# High_Current_Board.net
KiCad netlist of a schematic drawn in EAGLE
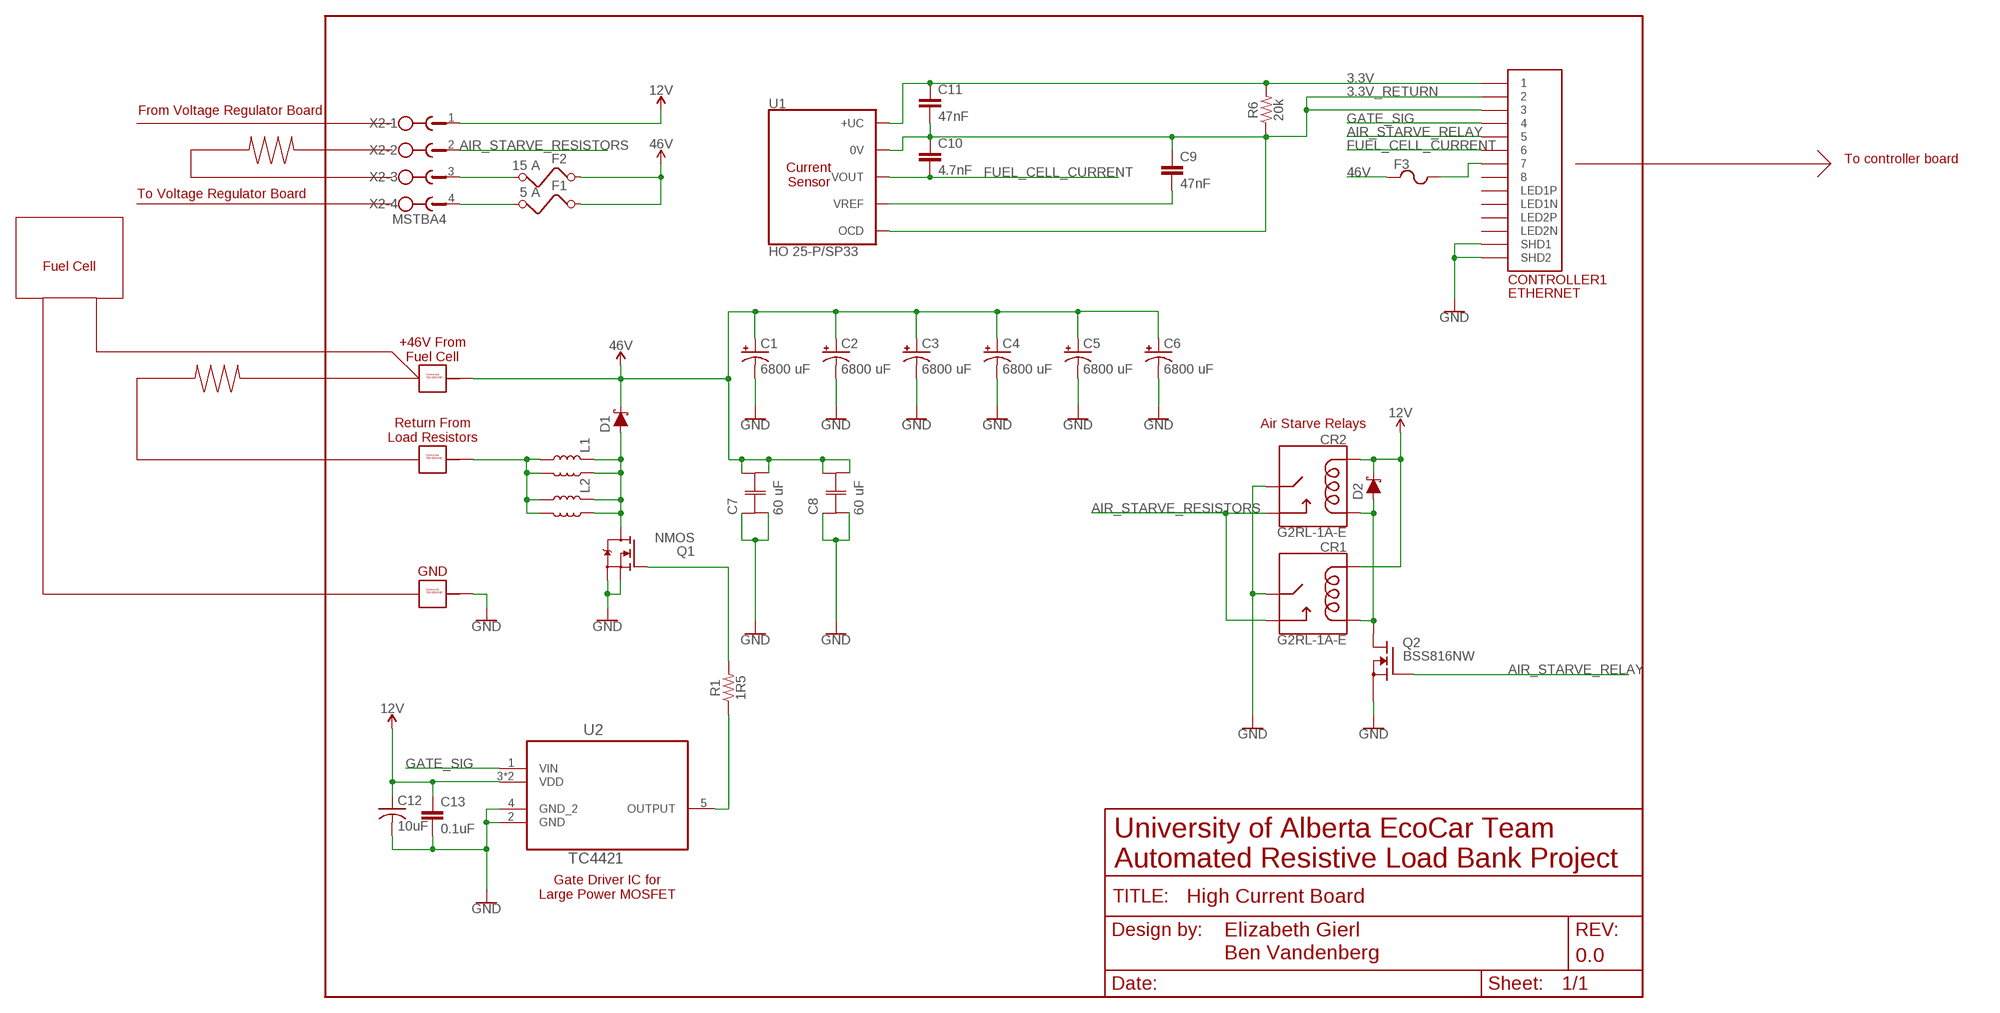
[diagram p0: schematic, sheet 1]

(export (version "E")
  (design (tool "Eeschema 10.0.6"))
  (components
    (comp (ref "C1")
      (value "6800 uF")
      (footprint "eagle-import:CPOL-RADIAL-10MM-35MM")
      (libsource (lib "eagle-import") (part "C-POL-RADIAL-10MM-35MM"))
    )
    (comp (ref "C2")
      (value "6800 uF")
      (footprint "eagle-import:CPOL-RADIAL-10MM-35MM")
      (libsource (lib "eagle-import") (part "C-POL-RADIAL-10MM-35MM"))
    )
    (comp (ref "C3")
      (value "6800 uF")
      (footprint "eagle-import:CPOL-RADIAL-10MM-35MM")
      (libsource (lib "eagle-import") (part "C-POL-RADIAL-10MM-35MM"))
    )
    (comp (ref "C4")
      (value "6800 uF")
      (footprint "eagle-import:CPOL-RADIAL-10MM-35MM")
      (libsource (lib "eagle-import") (part "C-POL-RADIAL-10MM-35MM"))
    )
    (comp (ref "C5")
      (value "6800 uF")
      (footprint "eagle-import:CPOL-RADIAL-10MM-35MM")
      (libsource (lib "eagle-import") (part "C-POL-RADIAL-10MM-35MM"))
    )
    (comp (ref "C6")
      (value "6800 uF")
      (footprint "eagle-import:CPOL-RADIAL-10MM-35MM")
      (libsource (lib "eagle-import") (part "C-POL-RADIAL-10MM-35MM"))
    )
    (comp (ref "C7")
      (value "60 uF")
      (footprint "eagle-import:C4A-0(60)")
      (fields (field (name "MANUFACTURER_PART_NUMBER") "C4ATDBW5600A30J"))
      (libsource (lib "eagle-import") (part "C4ATDBW5600A30J"))
    )
    (comp (ref "C8")
      (value "60 uF")
      (footprint "eagle-import:C4A-0(60)")
      (fields (field (name "MANUFACTURER_PART_NUMBER") "C4ATDBW5600A30J"))
      (libsource (lib "eagle-import") (part "C4ATDBW5600A30J"))
    )
    (comp (ref "C9")
      (value "47nF")
      (footprint "eagle-import:0805")
      (libsource (lib "eagle-import") (part "1.0UF-0805-25V-(+80/-20%)"))
    )
    (comp (ref "C10")
      (value "4.7nF")
      (footprint "eagle-import:0805")
      (libsource (lib "eagle-import") (part "1.0UF-0805-25V-(+80/-20%)"))
    )
    (comp (ref "C11")
      (value "47nF")
      (footprint "eagle-import:0805")
      (libsource (lib "eagle-import") (part "1.0UF-0805-25V-(+80/-20%)"))
    )
    (comp (ref "C12")
      (value "10uF")
      (footprint "eagle-import:C0603")
      (libsource (lib "eagle-import") (part "C-USC0603"))
    )
    (comp (ref "C13")
      (value "0.1uF")
      (footprint "eagle-import:0805")
      (libsource (lib "eagle-import") (part "1.0UF-0805-25V-(+80/-20%)"))
    )
    (comp (ref "CONTROLLER1")
      (value "ETHERNET")
      (footprint "eagle-import:A122645-ND")
      (libsource (lib "eagle-import") (part "ETHERNET"))
    )
    (comp (ref "CR1")
      (value "G2RL-1A-E")
      (footprint "eagle-import:G2RL-1A-E_RELAY")
      (libsource (lib "eagle-import") (part "G2RL-1A-E_SPST_RELAY"))
    )
    (comp (ref "CR2")
      (value "G2RL-1A-E")
      (footprint "eagle-import:G2RL-1A-E_RELAY")
      (libsource (lib "eagle-import") (part "G2RL-1A-E_SPST_RELAY"))
    )
    (comp (ref "D1")
      (value "VISHAY_VS-243NQ100PBF")
      (footprint "eagle-import:D-67_HALF-PAK")
      (libsource (lib "eagle-import") (part "VISHAY_VS-243NQ100PBF"))
    )
    (comp (ref "D2")
      (value "SOD-123F_SCHOTTKY")
      (footprint "eagle-import:SOD-123F")
      (libsource (lib "eagle-import") (part "SOD-123F_SCHOTTKY"))
    )
    (comp (ref "F1")
      (value "5 A")
      (footprint "eagle-import:KEYSTONE_ATM_FUSEHOLDER")
      (libsource (lib "eagle-import") (part "KEYSTONE_ATM_FUSEHOLDER"))
    )
    (comp (ref "F2")
      (value "15 A")
      (footprint "eagle-import:KEYSTONE_ATM_FUSEHOLDER")
      (libsource (lib "eagle-import") (part "KEYSTONE_ATM_FUSEHOLDER"))
    )
    (comp (ref "F3")
      (value "POLYFUSE")
      (footprint "eagle-import:1206")
      (libsource (lib "eagle-import") (part "POLYFUSE"))
    )
    (comp (ref "FC.GND1")
      (value "732-3204-ND_CONNECTOR")
      (footprint "eagle-import:732-3204-ND")
      (libsource (lib "eagle-import") (part "732-3204-ND_CONNECTOR"))
    )
    (comp (ref "FC.GND2")
      (value "732-3204-ND_CONNECTOR")
      (footprint "eagle-import:732-3204-ND")
      (libsource (lib "eagle-import") (part "732-3204-ND_CONNECTOR"))
    )
    (comp (ref "FC.POS")
      (value "732-3204-ND_CONNECTOR")
      (footprint "eagle-import:732-3204-ND")
      (libsource (lib "eagle-import") (part "732-3204-ND_CONNECTOR"))
    )
    (comp (ref "FRAME1")
      (value "FRAME-LETTERNO_PACKAGE")
      (footprint "eagle-import:DUMMY")
      (fields
        (field (name "DESIGNER") "Ben Vandenberg")
        (field (name "REV") "0.0")
        (field (name "DESIGNER_1") "Ben Vandenberg")
      )
      (libsource (lib "eagle-import") (part "FRAME-LETTERNO_PACKAGE"))
    )
    (comp (ref "L1")
      (value "CMX1616Z171B-10")
      (footprint "eagle-import:CMX1616Z171B-10")
      (libsource (lib "eagle-import") (part "CMX1616Z171B-10"))
    )
    (comp (ref "L2")
      (value "CMX1616Z171B-10")
      (footprint "eagle-import:CMX1616Z171B-10")
      (libsource (lib "eagle-import") (part "CMX1616Z171B-10"))
    )
    (comp (ref "Q1")
      (value "NMOS")
      (footprint "eagle-import:SOT-227")
      (libsource (lib "eagle-import") (part "VISHAY_BIG_MOSFET"))
    )
    (comp (ref "Q2")
      (value "BSS816NW")
      (footprint "eagle-import:SOT-323")
      (libsource (lib "eagle-import") (part "SOT323-NMOS"))
    )
    (comp (ref "R1")
      (value "1R5")
      (footprint "eagle-import:SMD_2512")
      (libsource (lib "eagle-import") (part "R_SMD_2512"))
    )
    (comp (ref "R6")
      (value "20k")
      (footprint "eagle-import:0805")
      (libsource (lib "eagle-import") (part "0.3OHM-0805-1/8W-1%"))
    )
    (comp (ref "U1")
      (value "HO 25-P/SP33")
      (footprint "eagle-import:LEM_HO_25-P")
      (libsource (lib "eagle-import") (part "LEM_HO_25-P"))
    )
    (comp (ref "U2")
      (value "TC4421")
      (footprint "eagle-import:TO220-52")
      (libsource (lib "eagle-import") (part "TC4421A-HORIZONTAL"))
    )
    (comp (ref "X2")
      (value "MSTBA4")
      (footprint "eagle-import:MSTBA4")
      (fields (field (name "MF") "FARNELL") (field (name "MPN") "1757268"))
      (libsource (lib "eagle-import") (part "MSTBA4"))
    )
  )
  (nets
    (net (code "1") (name "/3.3V") (class "Default")
      (node (ref "C11") (pin "1") (pinfunction "1_1") (pintype "passive"))
      (node (ref "CONTROLLER1") (pin "P$1") (pinfunction "1_P$1") (pintype "bidirectional"))
      (node (ref "R6") (pin "2") (pinfunction "2_2") (pintype "passive"))
      (node (ref "U1") (pin "1") (pinfunction "+UC_1") (pintype "passive"))
    )
    (net (code "2") (name "/3.3V_RETURN") (class "Default")
      (node (ref "C10") (pin "1") (pinfunction "1_1") (pintype "passive"))
      (node (ref "C11") (pin "2") (pinfunction "2_2") (pintype "passive"))
      (node (ref "C9") (pin "1") (pinfunction "1_1") (pintype "passive"))
      (node (ref "CONTROLLER1") (pin "P$2") (pinfunction "2_P$2") (pintype "bidirectional"))
      (node (ref "CONTROLLER1") (pin "P$3") (pinfunction "3_P$3") (pintype "bidirectional"))
      (node (ref "R6") (pin "1") (pinfunction "1_1") (pintype "passive"))
      (node (ref "U1") (pin "2") (pinfunction "0V_2") (pintype "passive"))
      (node (ref "U1") (pin "5") (pinfunction "OCD_5") (pintype "passive"))
    )
    (net (code "3") (name "/AIR_STARVE_RELAY") (class "Default")
      (node (ref "CONTROLLER1") (pin "P$5") (pinfunction "5_P$5") (pintype "bidirectional"))
      (node (ref "Q2") (pin "1G") (pinfunction "G_1G") (pintype "passive"))
    )
    (net (code "4") (name "/AIR_STARVE_RESISTORS") (class "Default")
      (node (ref "CR1") (pin "4") (pinfunction "NO_4") (pintype "bidirectional"))
      (node (ref "CR1") (pin "5") (pinfunction "NO_5") (pintype "bidirectional"))
      (node (ref "CR2") (pin "4") (pinfunction "NO_4") (pintype "bidirectional"))
      (node (ref "CR2") (pin "5") (pinfunction "NO_5") (pintype "bidirectional"))
      (node (ref "X2") (pin "2") (pinfunction "1_2") (pintype "passive"))
    )
    (net (code "5") (name "/FUEL_CELL_CURRENT") (class "Default")
      (node (ref "C10") (pin "2") (pinfunction "2_2") (pintype "passive"))
      (node (ref "CONTROLLER1") (pin "P$6") (pinfunction "6_P$6") (pintype "bidirectional"))
      (node (ref "U1") (pin "3") (pinfunction "VOUT_3") (pintype "passive"))
    )
    (net (code "6") (name "/GATE_SIG") (class "Default")
      (node (ref "CONTROLLER1") (pin "P$4") (pinfunction "4_P$4") (pintype "bidirectional"))
      (node (ref "U2") (pin "1") (pinfunction "VIN_1") (pintype "input"))
    )
    (net (code "7") (name "12V") (class "Default")
      (node (ref "C12") (pin "1") (pinfunction "1_1") (pintype "passive"))
      (node (ref "C13") (pin "1") (pinfunction "1_1") (pintype "passive"))
      (node (ref "CR1") (pin "1") (pinfunction "COIL1_1") (pintype "bidirectional"))
      (node (ref "CR2") (pin "1") (pinfunction "COIL1_1") (pintype "bidirectional"))
      (node (ref "D2") (pin "C") (pinfunction "C_C") (pintype "passive"))
      (node (ref "U2") (pin "3") (pinfunction "VDD_3") (pintype "power_in"))
      (node (ref "U2") (pin "P$1") (pinfunction "VDD_P$1") (pintype "power_in"))
      (node (ref "X2") (pin "1") (pinfunction "1_1") (pintype "passive"))
    )
    (net (code "8") (name "46V") (class "Default")
      (node (ref "C1") (pin "+") (pinfunction "+_+") (pintype "passive"))
      (node (ref "C2") (pin "+") (pinfunction "+_+") (pintype "passive"))
      (node (ref "C3") (pin "+") (pinfunction "+_+") (pintype "passive"))
      (node (ref "C4") (pin "+") (pinfunction "+_+") (pintype "passive"))
      (node (ref "C5") (pin "+") (pinfunction "+_+") (pintype "passive"))
      (node (ref "C6") (pin "+") (pinfunction "+_+") (pintype "passive"))
      (node (ref "C7") (pin "3") (pinfunction "3_3") (pintype "passive"))
      (node (ref "C7") (pin "4") (pinfunction "4_4") (pintype "passive"))
      (node (ref "C8") (pin "3") (pinfunction "3_3") (pintype "passive"))
      (node (ref "C8") (pin "4") (pinfunction "4_4") (pintype "passive"))
      (node (ref "D1") (pin "C") (pinfunction "C_C") (pintype "passive"))
      (node (ref "F1") (pin "L1") (pinfunction "1_L1") (pintype "passive"))
      (node (ref "F1") (pin "L2") (pinfunction "1_L2") (pintype "passive"))
      (node (ref "F2") (pin "L1") (pinfunction "1_L1") (pintype "passive"))
      (node (ref "F2") (pin "L2") (pinfunction "1_L2") (pintype "passive"))
      (node (ref "F3") (pin "1") (pinfunction "1_1") (pintype "passive"))
      (node (ref "FC.POS") (pin "P$1") (pinfunction "P$1_P$1") (pintype "bidirectional"))
      (node (ref "FC.POS") (pin "P$10") (pinfunction "P$1_P$10") (pintype "bidirectional"))
      (node (ref "FC.POS") (pin "P$2") (pinfunction "P$1_P$2") (pintype "bidirectional"))
      (node (ref "FC.POS") (pin "P$3") (pinfunction "P$1_P$3") (pintype "bidirectional"))
      (node (ref "FC.POS") (pin "P$4") (pinfunction "P$1_P$4") (pintype "bidirectional"))
      (node (ref "FC.POS") (pin "P$5") (pinfunction "P$1_P$5") (pintype "bidirectional"))
      (node (ref "FC.POS") (pin "P$6") (pinfunction "P$1_P$6") (pintype "bidirectional"))
      (node (ref "FC.POS") (pin "P$7") (pinfunction "P$1_P$7") (pintype "bidirectional"))
      (node (ref "FC.POS") (pin "P$8") (pinfunction "P$1_P$8") (pintype "bidirectional"))
      (node (ref "FC.POS") (pin "P$9") (pinfunction "P$1_P$9") (pintype "bidirectional"))
    )
    (net (code "9") (name "GND") (class "Default")
      (node (ref "C1") (pin "-") (pinfunction "-_-") (pintype "passive"))
      (node (ref "C12") (pin "2") (pinfunction "2_2") (pintype "passive"))
      (node (ref "C13") (pin "2") (pinfunction "2_2") (pintype "passive"))
      (node (ref "C2") (pin "-") (pinfunction "-_-") (pintype "passive"))
      (node (ref "C3") (pin "-") (pinfunction "-_-") (pintype "passive"))
      (node (ref "C4") (pin "-") (pinfunction "-_-") (pintype "passive"))
      (node (ref "C5") (pin "-") (pinfunction "-_-") (pintype "passive"))
      (node (ref "C6") (pin "-") (pinfunction "-_-") (pintype "passive"))
      (node (ref "C7") (pin "1") (pinfunction "1_1") (pintype "passive"))
      (node (ref "C7") (pin "2") (pinfunction "2_2") (pintype "passive"))
      (node (ref "C8") (pin "1") (pinfunction "1_1") (pintype "passive"))
      (node (ref "C8") (pin "2") (pinfunction "2_2") (pintype "passive"))
      (node (ref "CONTROLLER1") (pin "P$13") (pinfunction "SHD1_P$13") (pintype "bidirectional"))
      (node (ref "CONTROLLER1") (pin "P$14") (pinfunction "SHD2_P$14") (pintype "bidirectional"))
      (node (ref "CR1") (pin "3") (pinfunction "MAIN_3") (pintype "bidirectional"))
      (node (ref "CR1") (pin "6") (pinfunction "MAIN_6") (pintype "bidirectional"))
      (node (ref "CR2") (pin "3") (pinfunction "MAIN_3") (pintype "bidirectional"))
      (node (ref "CR2") (pin "6") (pinfunction "MAIN_6") (pintype "bidirectional"))
      (node (ref "FC.GND2") (pin "P$1") (pinfunction "P$1_P$1") (pintype "bidirectional"))
      (node (ref "FC.GND2") (pin "P$10") (pinfunction "P$1_P$10") (pintype "bidirectional"))
      (node (ref "FC.GND2") (pin "P$2") (pinfunction "P$1_P$2") (pintype "bidirectional"))
      (node (ref "FC.GND2") (pin "P$3") (pinfunction "P$1_P$3") (pintype "bidirectional"))
      (node (ref "FC.GND2") (pin "P$4") (pinfunction "P$1_P$4") (pintype "bidirectional"))
      (node (ref "FC.GND2") (pin "P$5") (pinfunction "P$1_P$5") (pintype "bidirectional"))
      (node (ref "FC.GND2") (pin "P$6") (pinfunction "P$1_P$6") (pintype "bidirectional"))
      (node (ref "FC.GND2") (pin "P$7") (pinfunction "P$1_P$7") (pintype "bidirectional"))
      (node (ref "FC.GND2") (pin "P$8") (pinfunction "P$1_P$8") (pintype "bidirectional"))
      (node (ref "FC.GND2") (pin "P$9") (pinfunction "P$1_P$9") (pintype "bidirectional"))
      (node (ref "Q1") (pin "S1") (pinfunction "S_S1") (pintype "passive"))
      (node (ref "Q1") (pin "S2") (pinfunction "S1_S2") (pintype "passive"))
      (node (ref "Q1") (pin "S3") (pinfunction "S_S3") (pintype "passive"))
      (node (ref "Q1") (pin "S4") (pinfunction "S1_S4") (pintype "passive"))
      (node (ref "Q2") (pin "2S") (pinfunction "S_2S") (pintype "passive"))
      (node (ref "U2") (pin "2") (pinfunction "GND_2") (pintype "passive"))
      (node (ref "U2") (pin "4") (pinfunction "GND_2_4") (pintype "passive"))
    )
    (net (code "10") (name "Net-(CONTROLLER1-7)") (class "Default")
      (node (ref "CONTROLLER1") (pin "P$7") (pinfunction "7_P$7") (pintype "bidirectional"))
      (node (ref "F3") (pin "2") (pinfunction "2_2") (pintype "passive"))
    )
    (net (code "11") (name "Net-(CR1-COIL2)") (class "Default")
      (node (ref "CR1") (pin "8") (pinfunction "COIL2_8") (pintype "bidirectional"))
      (node (ref "CR2") (pin "8") (pinfunction "COIL2_8") (pintype "bidirectional"))
      (node (ref "D2") (pin "A") (pinfunction "A_A") (pintype "passive"))
      (node (ref "Q2") (pin "3D") (pinfunction "D_3D") (pintype "passive"))
    )
    (net (code "12") (name "Net-(FC.GND1-P$1-PadP$10)") (class "Default")
      (node (ref "FC.GND1") (pin "P$1") (pinfunction "P$1_P$1") (pintype "bidirectional"))
      (node (ref "FC.GND1") (pin "P$10") (pinfunction "P$1_P$10") (pintype "bidirectional"))
      (node (ref "FC.GND1") (pin "P$2") (pinfunction "P$1_P$2") (pintype "bidirectional"))
      (node (ref "FC.GND1") (pin "P$3") (pinfunction "P$1_P$3") (pintype "bidirectional"))
      (node (ref "FC.GND1") (pin "P$4") (pinfunction "P$1_P$4") (pintype "bidirectional"))
      (node (ref "FC.GND1") (pin "P$5") (pinfunction "P$1_P$5") (pintype "bidirectional"))
      (node (ref "FC.GND1") (pin "P$6") (pinfunction "P$1_P$6") (pintype "bidirectional"))
      (node (ref "FC.GND1") (pin "P$7") (pinfunction "P$1_P$7") (pintype "bidirectional"))
      (node (ref "FC.GND1") (pin "P$8") (pinfunction "P$1_P$8") (pintype "bidirectional"))
      (node (ref "FC.GND1") (pin "P$9") (pinfunction "P$1_P$9") (pintype "bidirectional"))
      (node (ref "L1") (pin "R1") (pinfunction "B1_R1") (pintype "passive"))
      (node (ref "L1") (pin "R11") (pinfunction "B1_R11") (pintype "passive"))
      (node (ref "L1") (pin "R2") (pinfunction "B2_R2") (pintype "passive"))
      (node (ref "L1") (pin "R22") (pinfunction "B2_R22") (pintype "passive"))
      (node (ref "L2") (pin "R1") (pinfunction "B1_R1") (pintype "passive"))
      (node (ref "L2") (pin "R11") (pinfunction "B1_R11") (pintype "passive"))
      (node (ref "L2") (pin "R2") (pinfunction "B2_R2") (pintype "passive"))
      (node (ref "L2") (pin "R22") (pinfunction "B2_R22") (pintype "passive"))
    )
    (net (code "13") (name "Net-(L1-T1-PadL1)") (class "Default")
      (node (ref "L1") (pin "L1") (pinfunction "T1_L1") (pintype "passive"))
      (node (ref "L1") (pin "L11") (pinfunction "T1_L11") (pintype "passive"))
      (node (ref "L1") (pin "L2") (pinfunction "T2_L2") (pintype "passive"))
      (node (ref "L1") (pin "L22") (pinfunction "T2_L22") (pintype "passive"))
      (node (ref "L2") (pin "L1") (pinfunction "T1_L1") (pintype "passive"))
      (node (ref "L2") (pin "L11") (pinfunction "T1_L11") (pintype "passive"))
      (node (ref "L2") (pin "L2") (pinfunction "T2_L2") (pintype "passive"))
      (node (ref "L2") (pin "L22") (pinfunction "T2_L22") (pintype "passive"))
      (node (ref "Q1") (pin "D") (pinfunction "D_D") (pintype "passive"))
      (node (ref "Q1") (pin "D2") (pinfunction "D_D2") (pintype "passive"))
    )
    (net (code "14") (name "Net-(R1-1)") (class "Default")
      (node (ref "R1") (pin "P$1") (pinfunction "1_P$1") (pintype "passive"))
      (node (ref "U2") (pin "5") (pinfunction "OUTPUT_5") (pintype "output"))
    )
    (net (code "15") (name "Net-(R1-2)") (class "Default")
      (node (ref "Q1") (pin "G") (pinfunction "G_G") (pintype "passive"))
      (node (ref "Q1") (pin "G2") (pinfunction "G_G2") (pintype "passive"))
      (node (ref "R1") (pin "P$2") (pinfunction "2_P$2") (pintype "passive"))
    )
    (net (code "16") (name "Net-(U1-VREF)") (class "Default")
      (node (ref "C9") (pin "2") (pinfunction "2_2") (pintype "passive"))
      (node (ref "U1") (pin "4") (pinfunction "VREF_4") (pintype "passive"))
    )
    (net (code "17") (name "Net-(X2C-1)") (class "Default")
      (node (ref "F2") (pin "R1") (pinfunction "2_R1") (pintype "passive"))
      (node (ref "F2") (pin "R2") (pinfunction "2_R2") (pintype "passive"))
      (node (ref "X2") (pin "3") (pinfunction "1_3") (pintype "passive"))
    )
    (net (code "18") (name "Net-(X2D-1)") (class "Default")
      (node (ref "F1") (pin "R1") (pinfunction "2_R1") (pintype "passive"))
      (node (ref "F1") (pin "R2") (pinfunction "2_R2") (pintype "passive"))
      (node (ref "X2") (pin "4") (pinfunction "1_4") (pintype "passive"))
    )
    (net (code "19") (name "unconnected-(CONTROLLER1-8-PadP$8)") (class "Default")
      (node (ref "CONTROLLER1") (pin "P$8") (pinfunction "8_P$8") (pintype "bidirectional"))
    )
    (net (code "20") (name "unconnected-(CONTROLLER1-LED1N-PadP$9)") (class "Default")
      (node (ref "CONTROLLER1") (pin "P$9") (pinfunction "LED1N_P$9") (pintype "bidirectional"))
    )
    (net (code "21") (name "unconnected-(CONTROLLER1-LED1P-PadP$10)") (class "Default")
      (node (ref "CONTROLLER1") (pin "P$10") (pinfunction "LED1P_P$10") (pintype "bidirectional"))
    )
    (net (code "22") (name "unconnected-(CONTROLLER1-LED2N-PadP$11)") (class "Default")
      (node (ref "CONTROLLER1") (pin "P$11") (pinfunction "LED2N_P$11") (pintype "bidirectional"))
    )
    (net (code "23") (name "unconnected-(CONTROLLER1-LED2P-PadP$12)") (class "Default")
      (node (ref "CONTROLLER1") (pin "P$12") (pinfunction "LED2P_P$12") (pintype "bidirectional"))
    )
  )
)
